# Projekt.net
KiCad netlist of a schematic drawn in EAGLE
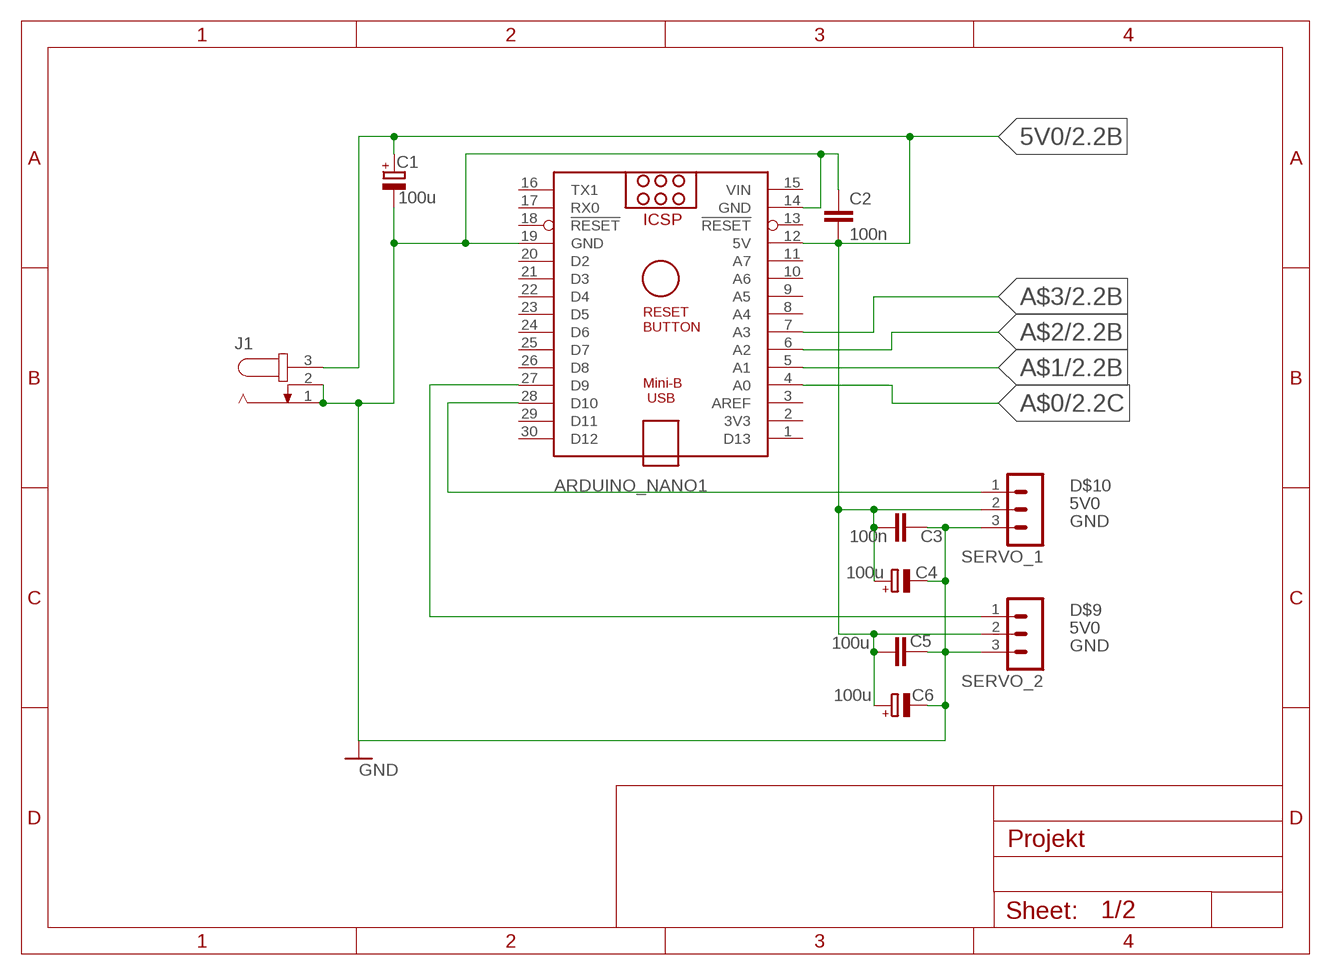
[diagram p0: schematic, sheet 1]
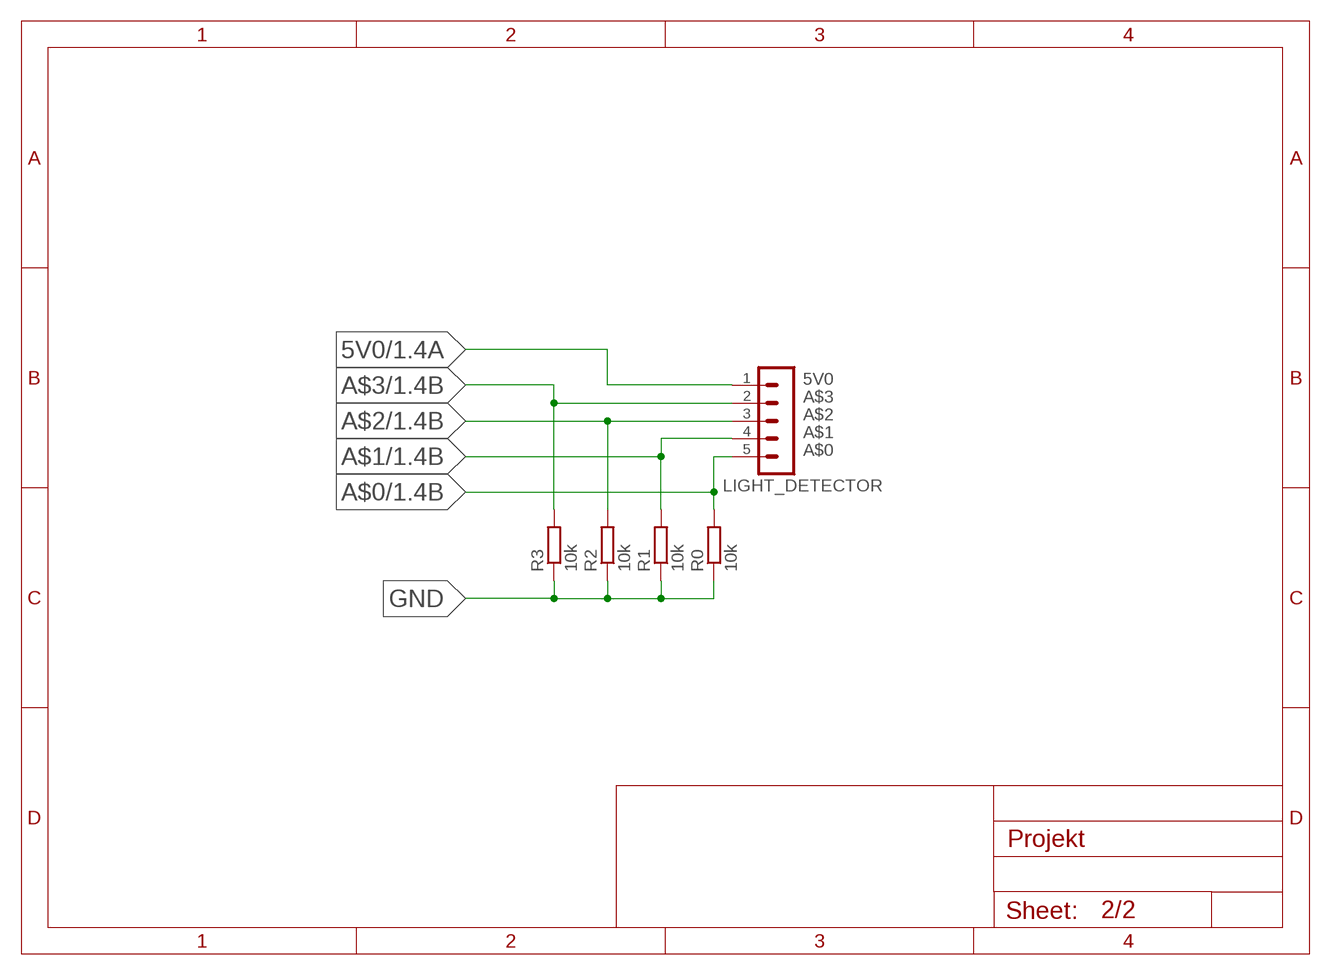
[diagram p1: schematic, sheet 2]

(export (version "E")
  (design (tool "Eeschema 10.0.6"))
  (components
    (comp (ref "LIGHT_DETECTOR")
      (value "MA05-1")
      (footprint "eagle-import:MA05-1")
      (libsource (lib "eagle-import") (part "MA05-1"))
    )
    (comp (ref "R0")
      (value "10k")
      (footprint "eagle-import:0207_10")
      (libsource (lib "eagle-import") (part "R-EU_0207/10"))
    )
    (comp (ref "R1")
      (value "10k")
      (footprint "eagle-import:0207_10")
      (libsource (lib "eagle-import") (part "R-EU_0207/10"))
    )
    (comp (ref "R2")
      (value "10k")
      (footprint "eagle-import:0207_10")
      (libsource (lib "eagle-import") (part "R-EU_0207/10"))
    )
    (comp (ref "R3")
      (value "10k")
      (footprint "eagle-import:0207_10")
      (libsource (lib "eagle-import") (part "R-EU_0207/10"))
    )
    (comp (ref "ARDUINO_NANO1")
      (value "ARDUINO_NANO")
      (footprint "eagle-import:ARDUINO_NANO")
      (libsource (lib "eagle-import") (part "ARDUINO_NANO"))
    )
    (comp (ref "C1")
      (value "100u")
      (footprint "eagle-import:E2,5-6E")
      (libsource (lib "eagle-import") (part "CPOL-EUE2,5-6E"))
    )
    (comp (ref "C2")
      (value "100n")
      (footprint "eagle-import:C050-024X044")
      (libsource (lib "eagle-import") (part "C-EU050-024X044"))
    )
    (comp (ref "C3")
      (value "100n")
      (footprint "eagle-import:C050-024X044")
      (libsource (lib "eagle-import") (part "C-EU050-024X044"))
    )
    (comp (ref "C4")
      (value "100u")
      (footprint "eagle-import:E2,5-6E")
      (libsource (lib "eagle-import") (part "CPOL-EUE2,5-6E"))
    )
    (comp (ref "C5")
      (value "100u")
      (footprint "eagle-import:C050-024X044")
      (libsource (lib "eagle-import") (part "C-EU050-024X044"))
    )
    (comp (ref "C6")
      (value "100u")
      (footprint "eagle-import:E2,5-6E")
      (libsource (lib "eagle-import") (part "CPOL-EUE2,5-6E"))
    )
    (comp (ref "J1")
      (value "JACK-PLUG0")
      (footprint "eagle-import:SPC4077")
      (libsource (lib "eagle-import") (part "JACK-PLUG0"))
    )
    (comp (ref "SERVO_1")
      (value "MA03-1")
      (footprint "eagle-import:MA03-1")
      (libsource (lib "eagle-import") (part "MA03-1"))
    )
    (comp (ref "SERVO_2")
      (value "MA03-1")
      (footprint "eagle-import:MA03-1")
      (libsource (lib "eagle-import") (part "MA03-1"))
    )
  )
  (nets
    (net (code "1") (name "5V0") (class "Default")
      (node (ref "ARDUINO_NANO1") (pin "12") (pinfunction "5V_12") (pintype "power_in"))
      (node (ref "C1") (pin "+") (pinfunction "+_+") (pintype "passive"))
      (node (ref "C2") (pin "2") (pinfunction "2_2") (pintype "passive"))
      (node (ref "C3") (pin "2") (pinfunction "2_2") (pintype "passive"))
      (node (ref "C4") (pin "+") (pinfunction "+_+") (pintype "passive"))
      (node (ref "C5") (pin "2") (pinfunction "2_2") (pintype "passive"))
      (node (ref "C6") (pin "+") (pinfunction "+_+") (pintype "passive"))
      (node (ref "J1") (pin "3") (pinfunction "3_3") (pintype "passive"))
      (node (ref "LIGHT_DETECTOR") (pin "1") (pinfunction "1_1") (pintype "passive"))
      (node (ref "SERVO_1") (pin "2") (pinfunction "2_2") (pintype "passive"))
      (node (ref "SERVO_2") (pin "2") (pinfunction "2_2") (pintype "passive"))
    )
    (net (code "2") (name "A$0") (class "Default")
      (node (ref "ARDUINO_NANO1") (pin "4") (pinfunction "A0_4") (pintype "bidirectional"))
      (node (ref "LIGHT_DETECTOR") (pin "5") (pinfunction "5_5") (pintype "passive"))
      (node (ref "R0") (pin "2") (pinfunction "2_2") (pintype "passive"))
    )
    (net (code "3") (name "A$1") (class "Default")
      (node (ref "ARDUINO_NANO1") (pin "5") (pinfunction "A1_5") (pintype "bidirectional"))
      (node (ref "LIGHT_DETECTOR") (pin "4") (pinfunction "4_4") (pintype "passive"))
      (node (ref "R1") (pin "2") (pinfunction "2_2") (pintype "passive"))
    )
    (net (code "4") (name "A$2") (class "Default")
      (node (ref "ARDUINO_NANO1") (pin "6") (pinfunction "A2_6") (pintype "bidirectional"))
      (node (ref "LIGHT_DETECTOR") (pin "3") (pinfunction "3_3") (pintype "passive"))
      (node (ref "R2") (pin "2") (pinfunction "2_2") (pintype "passive"))
    )
    (net (code "5") (name "A$3") (class "Default")
      (node (ref "ARDUINO_NANO1") (pin "7") (pinfunction "A3_7") (pintype "bidirectional"))
      (node (ref "LIGHT_DETECTOR") (pin "2") (pinfunction "2_2") (pintype "passive"))
      (node (ref "R3") (pin "2") (pinfunction "2_2") (pintype "passive"))
    )
    (net (code "6") (name "D$9") (class "Default")
      (node (ref "ARDUINO_NANO1") (pin "27") (pinfunction "D9_27") (pintype "bidirectional"))
      (node (ref "SERVO_2") (pin "1") (pinfunction "1_1") (pintype "passive"))
    )
    (net (code "7") (name "D$10") (class "Default")
      (node (ref "ARDUINO_NANO1") (pin "28") (pinfunction "D10_28") (pintype "bidirectional"))
      (node (ref "SERVO_1") (pin "1") (pinfunction "1_1") (pintype "passive"))
    )
    (net (code "8") (name "GND") (class "Default")
      (node (ref "ARDUINO_NANO1") (pin "14") (pinfunction "GND_14") (pintype "power_in"))
      (node (ref "ARDUINO_NANO1") (pin "19") (pinfunction "GND_19") (pintype "power_in"))
      (node (ref "C1") (pin "-") (pinfunction "-_-") (pintype "passive"))
      (node (ref "C2") (pin "1") (pinfunction "1_1") (pintype "passive"))
      (node (ref "C3") (pin "1") (pinfunction "1_1") (pintype "passive"))
      (node (ref "C4") (pin "-") (pinfunction "-_-") (pintype "passive"))
      (node (ref "C5") (pin "1") (pinfunction "1_1") (pintype "passive"))
      (node (ref "C6") (pin "-") (pinfunction "-_-") (pintype "passive"))
      (node (ref "J1") (pin "1") (pinfunction "1_1") (pintype "passive"))
      (node (ref "J1") (pin "2") (pinfunction "2_2") (pintype "passive"))
      (node (ref "R0") (pin "1") (pinfunction "1_1") (pintype "passive"))
      (node (ref "R1") (pin "1") (pinfunction "1_1") (pintype "passive"))
      (node (ref "R2") (pin "1") (pinfunction "1_1") (pintype "passive"))
      (node (ref "R3") (pin "1") (pinfunction "1_1") (pintype "passive"))
      (node (ref "SERVO_1") (pin "3") (pinfunction "3_3") (pintype "passive"))
      (node (ref "SERVO_2") (pin "3") (pinfunction "3_3") (pintype "passive"))
    )
    (net (code "9") (name "VIN") (class "Default")
      (node (ref "ARDUINO_NANO1") (pin "15") (pinfunction "VIN_15") (pintype "power_in"))
    )
    (net (code "10") (name "unconnected-(ARDUINO_NANO1-3V3-Pad2)") (class "Default")
      (node (ref "ARDUINO_NANO1") (pin "2") (pinfunction "3V3_2") (pintype "output"))
    )
    (net (code "11") (name "unconnected-(ARDUINO_NANO1-A4-Pad8)") (class "Default")
      (node (ref "ARDUINO_NANO1") (pin "8") (pinfunction "A4_8") (pintype "bidirectional"))
    )
    (net (code "12") (name "unconnected-(ARDUINO_NANO1-A5-Pad9)") (class "Default")
      (node (ref "ARDUINO_NANO1") (pin "9") (pinfunction "A5_9") (pintype "bidirectional"))
    )
    (net (code "13") (name "unconnected-(ARDUINO_NANO1-A6-Pad10)") (class "Default")
      (node (ref "ARDUINO_NANO1") (pin "10") (pinfunction "A6_10") (pintype "bidirectional"))
    )
    (net (code "14") (name "unconnected-(ARDUINO_NANO1-A7-Pad11)") (class "Default")
      (node (ref "ARDUINO_NANO1") (pin "11") (pinfunction "A7_11") (pintype "bidirectional"))
    )
    (net (code "15") (name "unconnected-(ARDUINO_NANO1-AREF-Pad3)") (class "Default")
      (node (ref "ARDUINO_NANO1") (pin "3") (pinfunction "AREF_3") (pintype "input"))
    )
    (net (code "16") (name "unconnected-(ARDUINO_NANO1-D2-Pad20)") (class "Default")
      (node (ref "ARDUINO_NANO1") (pin "20") (pinfunction "D2_20") (pintype "bidirectional"))
    )
    (net (code "17") (name "unconnected-(ARDUINO_NANO1-D3-Pad21)") (class "Default")
      (node (ref "ARDUINO_NANO1") (pin "21") (pinfunction "D3_21") (pintype "bidirectional"))
    )
    (net (code "18") (name "unconnected-(ARDUINO_NANO1-D4-Pad22)") (class "Default")
      (node (ref "ARDUINO_NANO1") (pin "22") (pinfunction "D4_22") (pintype "bidirectional"))
    )
    (net (code "19") (name "unconnected-(ARDUINO_NANO1-D5-Pad23)") (class "Default")
      (node (ref "ARDUINO_NANO1") (pin "23") (pinfunction "D5_23") (pintype "bidirectional"))
    )
    (net (code "20") (name "unconnected-(ARDUINO_NANO1-D6-Pad24)") (class "Default")
      (node (ref "ARDUINO_NANO1") (pin "24") (pinfunction "D6_24") (pintype "bidirectional"))
    )
    (net (code "21") (name "unconnected-(ARDUINO_NANO1-D7-Pad25)") (class "Default")
      (node (ref "ARDUINO_NANO1") (pin "25") (pinfunction "D7_25") (pintype "bidirectional"))
    )
    (net (code "22") (name "unconnected-(ARDUINO_NANO1-D8-Pad26)") (class "Default")
      (node (ref "ARDUINO_NANO1") (pin "26") (pinfunction "D8_26") (pintype "bidirectional"))
    )
    (net (code "23") (name "unconnected-(ARDUINO_NANO1-D11-Pad29)") (class "Default")
      (node (ref "ARDUINO_NANO1") (pin "29") (pinfunction "D11_29") (pintype "bidirectional"))
    )
    (net (code "24") (name "unconnected-(ARDUINO_NANO1-D12-Pad30)") (class "Default")
      (node (ref "ARDUINO_NANO1") (pin "30") (pinfunction "D12_30") (pintype "bidirectional"))
    )
    (net (code "25") (name "unconnected-(ARDUINO_NANO1-D13-Pad1)") (class "Default")
      (node (ref "ARDUINO_NANO1") (pin "1") (pinfunction "D13_1") (pintype "bidirectional"))
    )
    (net (code "26") (name "unconnected-(ARDUINO_NANO1-RX0-Pad17)") (class "Default")
      (node (ref "ARDUINO_NANO1") (pin "17") (pinfunction "RX0_17") (pintype "bidirectional"))
    )
    (net (code "27") (name "unconnected-(ARDUINO_NANO1-TX1-Pad16)") (class "Default")
      (node (ref "ARDUINO_NANO1") (pin "16") (pinfunction "TX1_16") (pintype "bidirectional"))
    )
    (net (code "28") (name "unconnected-(ARDUINO_NANO1-~{RESET}-Pad13)") (class "Default")
      (node (ref "ARDUINO_NANO1") (pin "13") (pinfunction "~{RESET}_13") (pintype "input"))
    )
    (net (code "29") (name "unconnected-(ARDUINO_NANO1-~{RESET}-Pad18)") (class "Default")
      (node (ref "ARDUINO_NANO1") (pin "18") (pinfunction "~{RESET}_18") (pintype "input"))
    )
  )
)
